# 07_-_USB-hub.net
KiCad netlist of a schematic drawn in Altium Designer
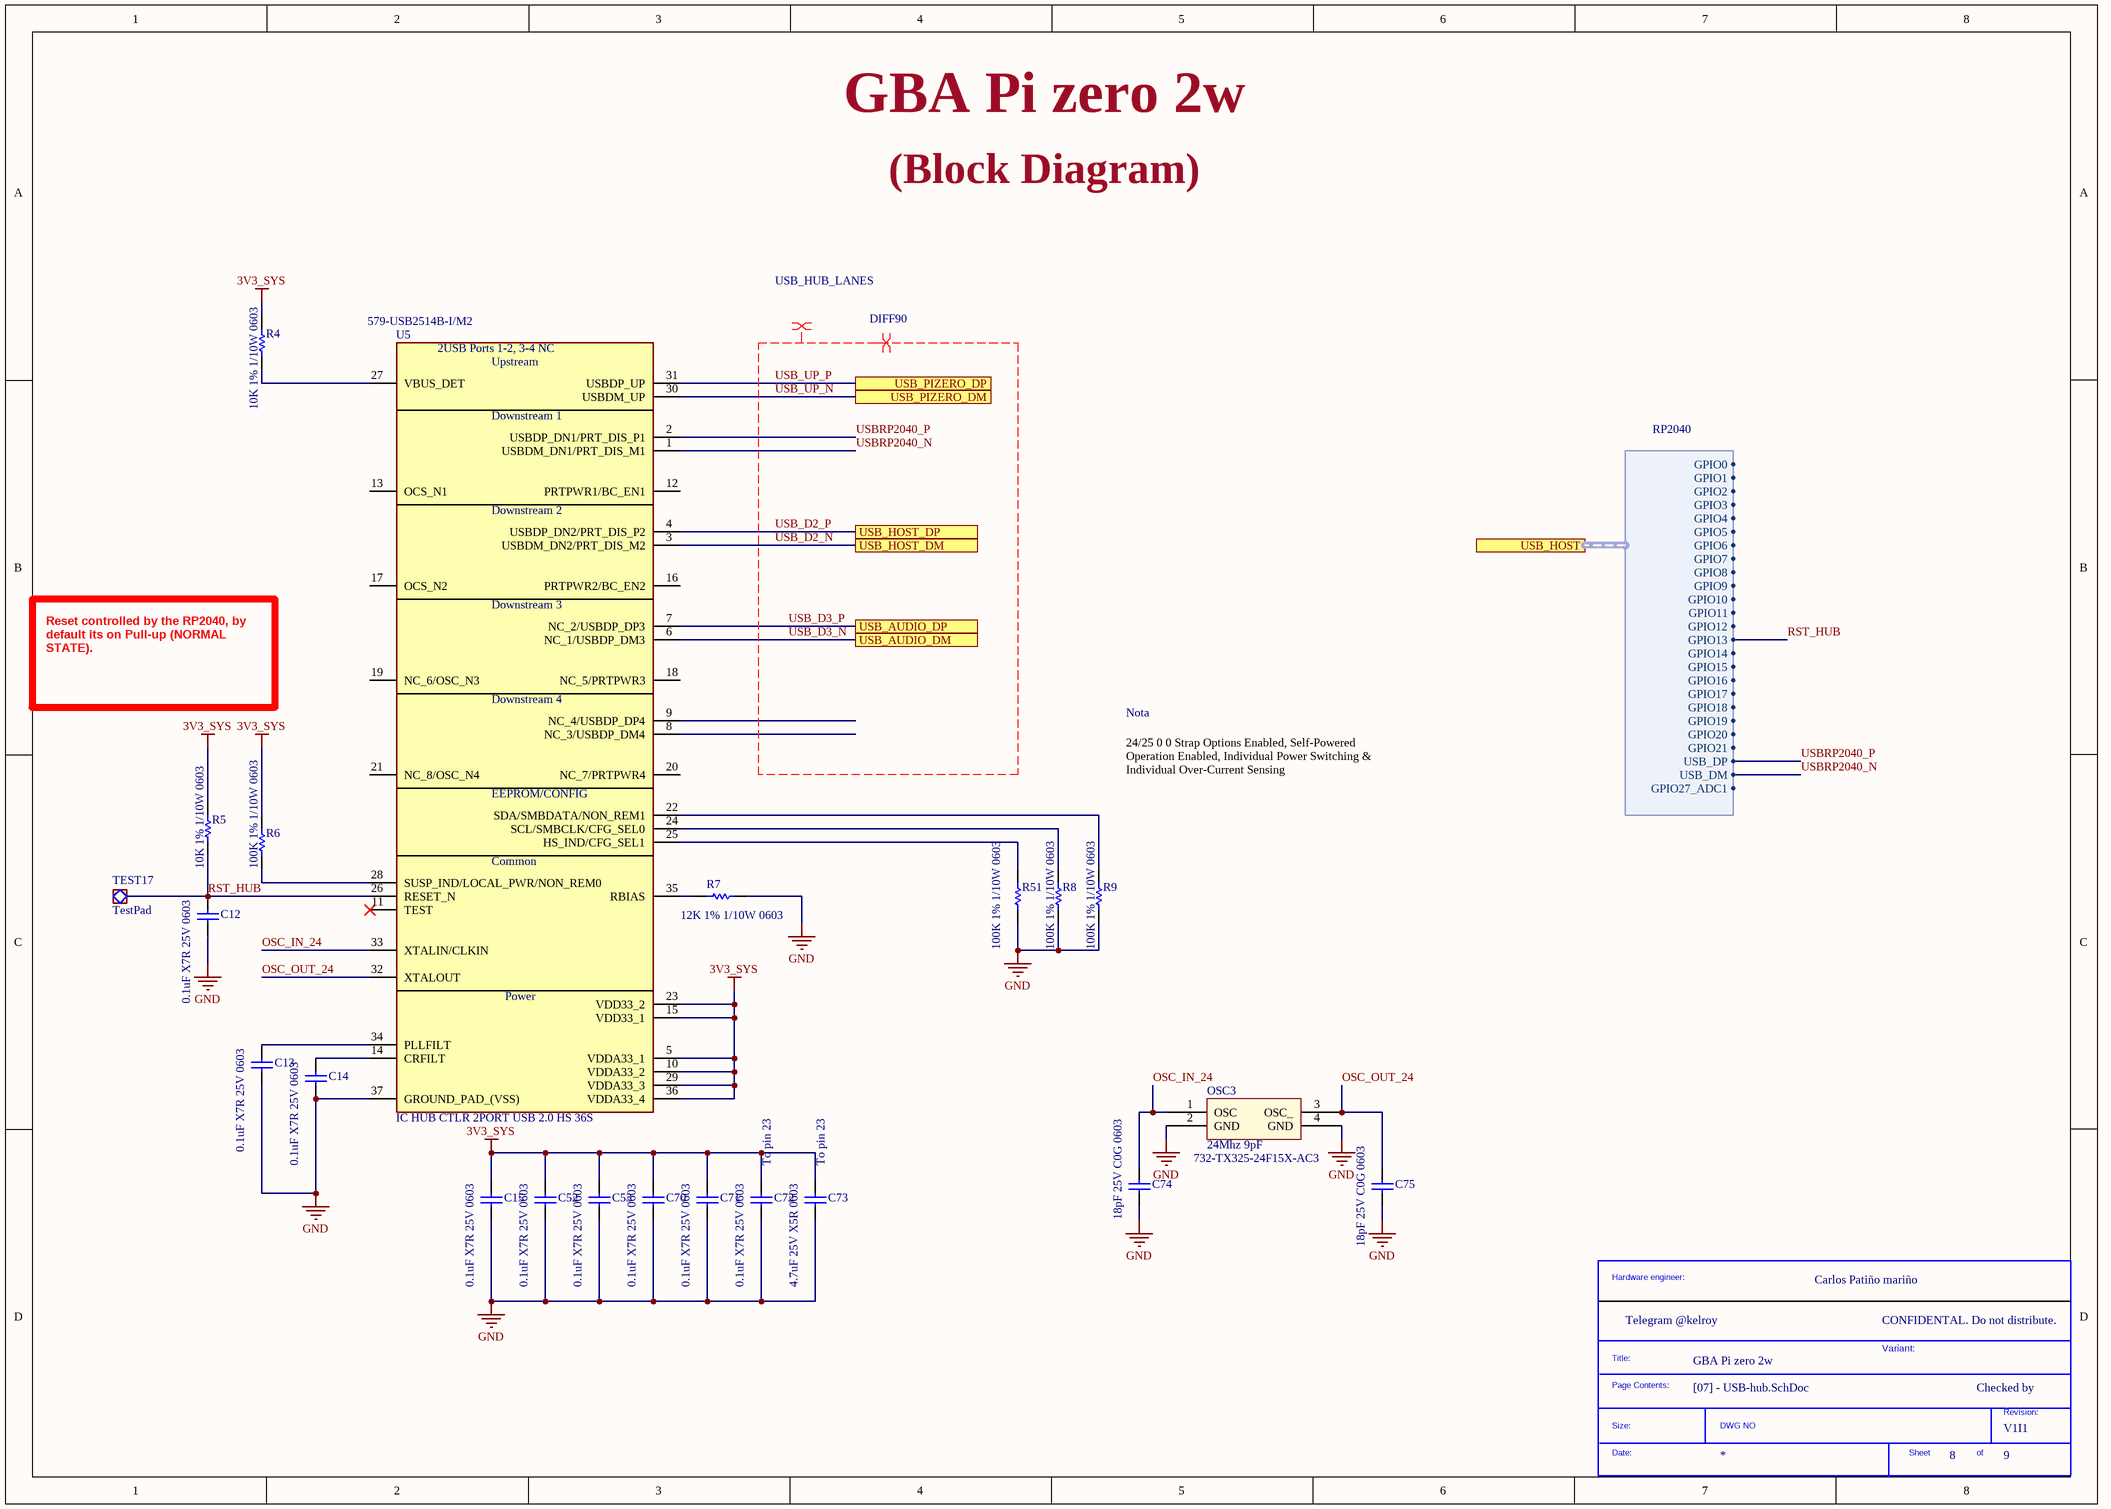
[diagram p0: [07] - USB-hub.SchDoc]

(export (version "E")
  (design (tool "Eeschema 10.0.6"))
  (components
    (comp (ref "C12")
      (value "0.1uF X7R 25V 0603")
      (footprint "C 0603/1608")
      (fields
        (field (name "MANUFACTURER") "Wurth Electronics")
        (field (name "MANUFACTURER PART NUMBER") "885012206071")
        (field (name "TOLERANCE") "10%")
      )
      (libsource (lib "altium-import") (part "root_1_885012206071_"))
    )
    (comp (ref "C13")
      (value "0.1uF X7R 25V 0603")
      (footprint "C 0603/1608")
      (fields
        (field (name "MANUFACTURER") "Wurth Electronics")
        (field (name "MANUFACTURER PART NUMBER") "885012206071")
        (field (name "TOLERANCE") "10%")
      )
      (libsource (lib "altium-import") (part "root_1_885012206071_"))
    )
    (comp (ref "C14")
      (value "0.1uF X7R 25V 0603")
      (footprint "C 0603/1608")
      (fields
        (field (name "MANUFACTURER") "Wurth Electronics")
        (field (name "MANUFACTURER PART NUMBER") "885012206071")
        (field (name "TOLERANCE") "10%")
      )
      (libsource (lib "altium-import") (part "root_1_885012206071_"))
    )
    (comp (ref "C15")
      (value "0.1uF X7R 25V 0603")
      (footprint "C 0603/1608")
      (fields
        (field (name "MANUFACTURER") "Wurth Electronics")
        (field (name "MANUFACTURER PART NUMBER") "885012206071")
        (field (name "TOLERANCE") "10%")
      )
      (libsource (lib "altium-import") (part "root_1_885012206071_"))
    )
    (comp (ref "C52")
      (value "0.1uF X7R 25V 0603")
      (footprint "C 0603/1608")
      (fields
        (field (name "MANUFACTURER") "Wurth Electronics")
        (field (name "MANUFACTURER PART NUMBER") "885012206071")
        (field (name "TOLERANCE") "10%")
      )
      (libsource (lib "altium-import") (part "root_1_885012206071_"))
    )
    (comp (ref "C53")
      (value "0.1uF X7R 25V 0603")
      (footprint "C 0603/1608")
      (fields
        (field (name "MANUFACTURER") "Wurth Electronics")
        (field (name "MANUFACTURER PART NUMBER") "885012206071")
        (field (name "TOLERANCE") "10%")
      )
      (libsource (lib "altium-import") (part "root_1_885012206071_"))
    )
    (comp (ref "C70")
      (value "0.1uF X7R 25V 0603")
      (footprint "C 0603/1608")
      (fields
        (field (name "MANUFACTURER") "Wurth Electronics")
        (field (name "MANUFACTURER PART NUMBER") "885012206071")
        (field (name "TOLERANCE") "10%")
      )
      (libsource (lib "altium-import") (part "root_1_885012206071_"))
    )
    (comp (ref "C71")
      (value "0.1uF X7R 25V 0603")
      (footprint "C 0603/1608")
      (fields
        (field (name "MANUFACTURER") "Wurth Electronics")
        (field (name "MANUFACTURER PART NUMBER") "885012206071")
        (field (name "TOLERANCE") "10%")
      )
      (libsource (lib "altium-import") (part "root_1_885012206071_"))
    )
    (comp (ref "C72")
      (value "0.1uF X7R 25V 0603")
      (footprint "C 0603/1608")
      (fields
        (field (name "MANUFACTURER") "Wurth Electronics")
        (field (name "MANUFACTURER PART NUMBER") "885012206071")
        (field (name "TOLERANCE") "10%")
      )
      (libsource (lib "altium-import") (part "root_1_885012206071_"))
    )
    (comp (ref "C73")
      (value "4.7uF 25V X5R 0603")
      (footprint "C 0603/1608")
      (description "Condensadores de cerámica multicapa (MLCC- SMD/SMT) 0603 25VDC 4.7uF 20% X5R")
      (libsource (lib "Kelboy") (part "TMK107BBJ475MA-T"))
    )
    (comp (ref "C74")
      (value "18pF 25V C0G 0603")
      (footprint "C 0603/1608")
      (description "Cap Ceramic 18pF 25V C0G 5% SMD 0603 125C Paper T/R")
      (fields (field (name "TOLERANCE") "5%"))
      (libsource (lib "USB_Host") (part "CC0603JRNPO8BN180"))
    )
    (comp (ref "C75")
      (value "18pF 25V C0G 0603")
      (footprint "C 0603/1608")
      (description "Cap Ceramic 18pF 25V C0G 5% SMD 0603 125C Paper T/R")
      (fields (field (name "TOLERANCE") "5%"))
      (libsource (lib "USB_Host") (part "CC0603JRNPO8BN180"))
    )
    (comp (ref "OSC3")
      (value "24Mhz 9pF")
      (footprint "3.2 mm x 2.5 mm(SMD 3225")
      (description "CRYSTAL 24.0000MHZ 9PF SMD")
      (fields
        (field (name "TOLERANCE") "10ppm")
        (field (name "SUPPLIER PART NUMBER 1") "732-TX325-24F15X-AC3")
      )
      (libsource (lib "USB_Host") (part "TSX-322524.0000MF15X-AC3"))
    )
    (comp (ref "R4")
      (value "10K 1% 1/10W 0603")
      (footprint "R 0603/1608")
      (description "RES SMD 10K OHM 1% 1/10W 0603")
      (fields
        (field (name "MANUFACTURER") "Yageo")
        (field (name "MANUFACTURER PART NUMBER") "RC0603FR-0710KL")
      )
      (libsource (lib "altium-import") (part "root_1_RC0603FR-0710KL_"))
    )
    (comp (ref "R5")
      (value "10K 1% 1/10W 0603")
      (footprint "R 0603/1608")
      (description "RES SMD 10K OHM 1% 1/10W 0603")
      (fields
        (field (name "MANUFACTURER") "Yageo")
        (field (name "MANUFACTURER PART NUMBER") "RC0603FR-0710KL")
      )
      (libsource (lib "altium-import") (part "root_1_RC0603FR-0710KL_"))
    )
    (comp (ref "R6")
      (value "100K 1% 1/10W 0603")
      (footprint "R 0603/1608")
      (description "RES SMD 100K OHM 1% 1/10W 0603")
      (fields
        (field (name "MANUFACTURER") "Yageo")
        (field (name "MANUFACTURER PART NUMBER") "RC0603FR-07100KL")
      )
      (libsource (lib "altium-import") (part "root_1_RC0603FR-07100KL_"))
    )
    (comp (ref "R7")
      (value "12K 1% 1/10W 0603")
      (footprint "R 0603/1608")
      (description "RES SMD 12K OHM 1% 1/10W 0603")
      (fields
        (field (name "MANUFACTURER") "Yageo")
        (field (name "MANUFACTURER PART NUMBER") "RC0603FR-0712KL")
      )
      (libsource (lib "altium-import") (part "root_0_RC0603FR-0712KL_"))
    )
    (comp (ref "R8")
      (value "100K 1% 1/10W 0603")
      (footprint "R 0603/1608")
      (description "RES SMD 100K OHM 1% 1/10W 0603")
      (fields
        (field (name "MANUFACTURER") "Yageo")
        (field (name "MANUFACTURER PART NUMBER") "RC0603FR-07100KL")
      )
      (libsource (lib "altium-import") (part "root_1_RC0603FR-07100KL_"))
    )
    (comp (ref "R9")
      (value "100K 1% 1/10W 0603")
      (footprint "R 0603/1608")
      (description "RES SMD 100K OHM 1% 1/10W 0603")
      (fields
        (field (name "MANUFACTURER") "Yageo")
        (field (name "MANUFACTURER PART NUMBER") "RC0603FR-07100KL")
      )
      (libsource (lib "altium-import") (part "root_1_RC0603FR-07100KL_"))
    )
    (comp (ref "R51")
      (value "100K 1% 1/10W 0603")
      (footprint "R 0603/1608")
      (description "RES SMD 100K OHM 1% 1/10W 0603")
      (fields
        (field (name "MANUFACTURER") "Yageo")
        (field (name "MANUFACTURER PART NUMBER") "RC0603FR-07100KL")
      )
      (libsource (lib "altium-import") (part "root_1_RC0603FR-07100KL_"))
    )
    (comp (ref "TEST17")
      (value "TestPad")
      (footprint "TestPad")
      (description "Probe Pad, SMT, ROUND, 2.0MM")
      (libsource (lib "altium-import") (part "root_2_PP_SMT_ROUND_2MM_"))
    )
    (comp (ref "U5")
      (value "IC HUB CTLR 2PORT USB 2.0 HS 36S")
      (footprint "QFN50P600X600X100-37N-D")
      (fields (field (name "SUPPLIER PART NUMBER 1") "579-USB2514B-I/M2"))
      (libsource (lib "USB_Host") (part "USB2512B/M2"))
    )
  )
  (nets
    (net (code "2") (name "/OSC_IN_24") (class "Default")
      (node (ref "C74") (pin "1") (pinfunction "1_1") (pintype "passive"))
      (node (ref "OSC3") (pin "1") (pinfunction "OSC_1") (pintype "passive"))
      (node (ref "U5") (pin "33") (pinfunction "XTALIN/CLKIN_33") (pintype "passive"))
    )
    (net (code "3") (name "/OSC_OUT_24") (class "Default")
      (node (ref "C75") (pin "1") (pinfunction "1_1") (pintype "passive"))
      (node (ref "OSC3") (pin "3") (pinfunction "OSC__3") (pintype "passive"))
      (node (ref "U5") (pin "32") (pinfunction "XTALOUT_32") (pintype "passive"))
    )
    (net (code "4") (name "/RST_HUB") (class "Default")
      (node (ref "C12") (pin "1") (pinfunction "1_1") (pintype "passive"))
      (node (ref "R5") (pin "1") (pinfunction "1_1") (pintype "passive"))
      (node (ref "TEST17") (pin "1") (pinfunction "1_1") (pintype "passive"))
      (node (ref "U5") (pin "26") (pinfunction "RESET_N_26") (pintype "passive"))
    )
    (net (code "5") (name "/USBRP2040_N") (class "Default")
      (node (ref "U5") (pin "1") (pinfunction "USBDM_DN1/PRT_DIS_M1_1") (pintype "passive"))
    )
    (net (code "6") (name "/USBRP2040_P") (class "Default")
      (node (ref "U5") (pin "2") (pinfunction "USBDP_DN1/PRT_DIS_P1_2") (pintype "passive"))
    )
    (net (code "7") (name "/USB_D2_N") (class "Default")
      (node (ref "U5") (pin "3") (pinfunction "USBDM_DN2/PRT_DIS_M2_3") (pintype "passive"))
    )
    (net (code "8") (name "/USB_D2_P") (class "Default")
      (node (ref "U5") (pin "4") (pinfunction "USBDP_DN2/PRT_DIS_P2_4") (pintype "passive"))
    )
    (net (code "9") (name "/USB_D3_N") (class "Default")
      (node (ref "U5") (pin "6") (pinfunction "NC_1/USBDP_DM3_6") (pintype "passive"))
    )
    (net (code "10") (name "/USB_D3_P") (class "Default")
      (node (ref "U5") (pin "7") (pinfunction "NC_2/USBDP_DP3_7") (pintype "passive"))
    )
    (net (code "11") (name "/USB_UP_N") (class "Default")
      (node (ref "U5") (pin "30") (pinfunction "USBDM_UP_30") (pintype "passive"))
    )
    (net (code "12") (name "/USB_UP_P") (class "Default")
      (node (ref "U5") (pin "31") (pinfunction "USBDP_UP_31") (pintype "passive"))
    )
    (net (code "14") (name "3V3_SYS") (class "Default")
      (node (ref "C15") (pin "1") (pinfunction "1_1") (pintype "passive"))
      (node (ref "C52") (pin "1") (pinfunction "1_1") (pintype "passive"))
      (node (ref "C53") (pin "1") (pinfunction "1_1") (pintype "passive"))
      (node (ref "C70") (pin "1") (pinfunction "1_1") (pintype "passive"))
      (node (ref "C71") (pin "1") (pinfunction "1_1") (pintype "passive"))
      (node (ref "C72") (pin "1") (pinfunction "1_1") (pintype "passive"))
      (node (ref "C73") (pin "1") (pinfunction "1_1") (pintype "passive"))
      (node (ref "R4") (pin "2") (pinfunction "2_2") (pintype "passive"))
      (node (ref "R5") (pin "2") (pinfunction "2_2") (pintype "passive"))
      (node (ref "R6") (pin "2") (pinfunction "2_2") (pintype "passive"))
      (node (ref "U5") (pin "10") (pinfunction "VDDA33_2_10") (pintype "passive"))
      (node (ref "U5") (pin "15") (pinfunction "VDD33_1_15") (pintype "passive"))
      (node (ref "U5") (pin "23") (pinfunction "VDD33_2_23") (pintype "passive"))
      (node (ref "U5") (pin "29") (pinfunction "VDDA33_3_29") (pintype "passive"))
      (node (ref "U5") (pin "36") (pinfunction "VDDA33_4_36") (pintype "passive"))
      (node (ref "U5") (pin "5") (pinfunction "VDDA33_1_5") (pintype "passive"))
    )
    (net (code "15") (name "GND") (class "Default")
      (node (ref "C12") (pin "2") (pinfunction "2_2") (pintype "passive"))
      (node (ref "C13") (pin "2") (pinfunction "2_2") (pintype "passive"))
      (node (ref "C14") (pin "2") (pinfunction "2_2") (pintype "passive"))
      (node (ref "C15") (pin "2") (pinfunction "2_2") (pintype "passive"))
      (node (ref "C52") (pin "2") (pinfunction "2_2") (pintype "passive"))
      (node (ref "C53") (pin "2") (pinfunction "2_2") (pintype "passive"))
      (node (ref "C70") (pin "2") (pinfunction "2_2") (pintype "passive"))
      (node (ref "C71") (pin "2") (pinfunction "2_2") (pintype "passive"))
      (node (ref "C72") (pin "2") (pinfunction "2_2") (pintype "passive"))
      (node (ref "C73") (pin "2") (pinfunction "2_2") (pintype "passive"))
      (node (ref "C74") (pin "2") (pinfunction "2_2") (pintype "passive"))
      (node (ref "C75") (pin "2") (pinfunction "2_2") (pintype "passive"))
      (node (ref "OSC3") (pin "2") (pinfunction "GND_2") (pintype "passive"))
      (node (ref "OSC3") (pin "4") (pinfunction "GND_4") (pintype "passive"))
      (node (ref "R51") (pin "1") (pinfunction "1_1") (pintype "passive"))
      (node (ref "R7") (pin "2") (pinfunction "2_2") (pintype "passive"))
      (node (ref "R8") (pin "1") (pinfunction "1_1") (pintype "passive"))
      (node (ref "R9") (pin "1") (pinfunction "1_1") (pintype "passive"))
      (node (ref "U5") (pin "37") (pinfunction "GROUND_PAD_(VSS)_37") (pintype "passive"))
    )
    (net (code "16") (name "Net-(U5-CRFILT)") (class "Default")
      (node (ref "C14") (pin "1") (pinfunction "1_1") (pintype "passive"))
      (node (ref "U5") (pin "14") (pinfunction "CRFILT_14") (pintype "passive"))
    )
    (net (code "17") (name "Net-(U5-HS_IND{slash}CFG_SEL1)") (class "Default")
      (node (ref "R51") (pin "2") (pinfunction "2_2") (pintype "passive"))
      (node (ref "U5") (pin "25") (pinfunction "HS_IND/CFG_SEL1_25") (pintype "passive"))
    )
    (net (code "18") (name "Net-(U5-PLLFILT)") (class "Default")
      (node (ref "C13") (pin "1") (pinfunction "1_1") (pintype "passive"))
      (node (ref "U5") (pin "34") (pinfunction "PLLFILT_34") (pintype "passive"))
    )
    (net (code "19") (name "Net-(U5-RBIAS)") (class "Default")
      (node (ref "R7") (pin "1") (pinfunction "1_1") (pintype "passive"))
      (node (ref "U5") (pin "35") (pinfunction "RBIAS_35") (pintype "passive"))
    )
    (net (code "20") (name "Net-(U5-SCL{slash}SMBCLK{slash}CFG_SEL0)") (class "Default")
      (node (ref "R8") (pin "2") (pinfunction "2_2") (pintype "passive"))
      (node (ref "U5") (pin "24") (pinfunction "SCL/SMBCLK/CFG_SEL0_24") (pintype "passive"))
    )
    (net (code "21") (name "Net-(U5-SDA{slash}SMBDATA{slash}NON_REM1)") (class "Default")
      (node (ref "R9") (pin "2") (pinfunction "2_2") (pintype "passive"))
      (node (ref "U5") (pin "22") (pinfunction "SDA/SMBDATA/NON_REM1_22") (pintype "passive"))
    )
    (net (code "22") (name "Net-(U5-SUSP_IND{slash}LOCAL_PWR{slash}NON_REM0)") (class "Default")
      (node (ref "R6") (pin "1") (pinfunction "1_1") (pintype "passive"))
      (node (ref "U5") (pin "28") (pinfunction "SUSP_IND/LOCAL_PWR/NON_REM0_28") (pintype "passive"))
    )
    (net (code "23") (name "Net-(U5-VBUS_DET)") (class "Default")
      (node (ref "R4") (pin "1") (pinfunction "1_1") (pintype "passive"))
      (node (ref "U5") (pin "27") (pinfunction "VBUS_DET_27") (pintype "passive"))
    )
    (net (code "24") (name "unconnected-(U5-NC_3{slash}USBDP_DM4-Pad8)") (class "Default")
      (node (ref "U5") (pin "8") (pinfunction "NC_3/USBDP_DM4_8") (pintype "passive"))
    )
    (net (code "25") (name "unconnected-(U5-NC_4{slash}USBDP_DP4-Pad9)") (class "Default")
      (node (ref "U5") (pin "9") (pinfunction "NC_4/USBDP_DP4_9") (pintype "passive"))
    )
    (net (code "26") (name "unconnected-(U5-NC_5{slash}PRTPWR3-Pad18)") (class "Default")
      (node (ref "U5") (pin "18") (pinfunction "NC_5/PRTPWR3_18") (pintype "passive"))
    )
    (net (code "27") (name "unconnected-(U5-NC_6{slash}OSC_N3-Pad19)") (class "Default")
      (node (ref "U5") (pin "19") (pinfunction "NC_6/OSC_N3_19") (pintype "passive"))
    )
    (net (code "28") (name "unconnected-(U5-NC_7{slash}PRTPWR4-Pad20)") (class "Default")
      (node (ref "U5") (pin "20") (pinfunction "NC_7/PRTPWR4_20") (pintype "passive"))
    )
    (net (code "29") (name "unconnected-(U5-NC_8{slash}OSC_N4-Pad21)") (class "Default")
      (node (ref "U5") (pin "21") (pinfunction "NC_8/OSC_N4_21") (pintype "passive"))
    )
    (net (code "30") (name "unconnected-(U5-OCS_N1-Pad13)") (class "Default")
      (node (ref "U5") (pin "13") (pinfunction "OCS_N1_13") (pintype "passive"))
    )
    (net (code "31") (name "unconnected-(U5-OCS_N2-Pad17)") (class "Default")
      (node (ref "U5") (pin "17") (pinfunction "OCS_N2_17") (pintype "passive"))
    )
    (net (code "32") (name "unconnected-(U5-PRTPWR1{slash}BC_EN1-Pad12)") (class "Default")
      (node (ref "U5") (pin "12") (pinfunction "PRTPWR1/BC_EN1_12") (pintype "passive"))
    )
    (net (code "33") (name "unconnected-(U5-PRTPWR2{slash}BC_EN2-Pad16)") (class "Default")
      (node (ref "U5") (pin "16") (pinfunction "PRTPWR2/BC_EN2_16") (pintype "passive"))
    )
    (net (code "34") (name "unconnected-(U5-TEST-Pad11)") (class "Default")
      (node (ref "U5") (pin "11") (pinfunction "TEST_11") (pintype "passive+no_connect"))
    )
  )
)
